# IRQF103C8revA.net
KiCad netlist of a schematic drawn in EAGLE
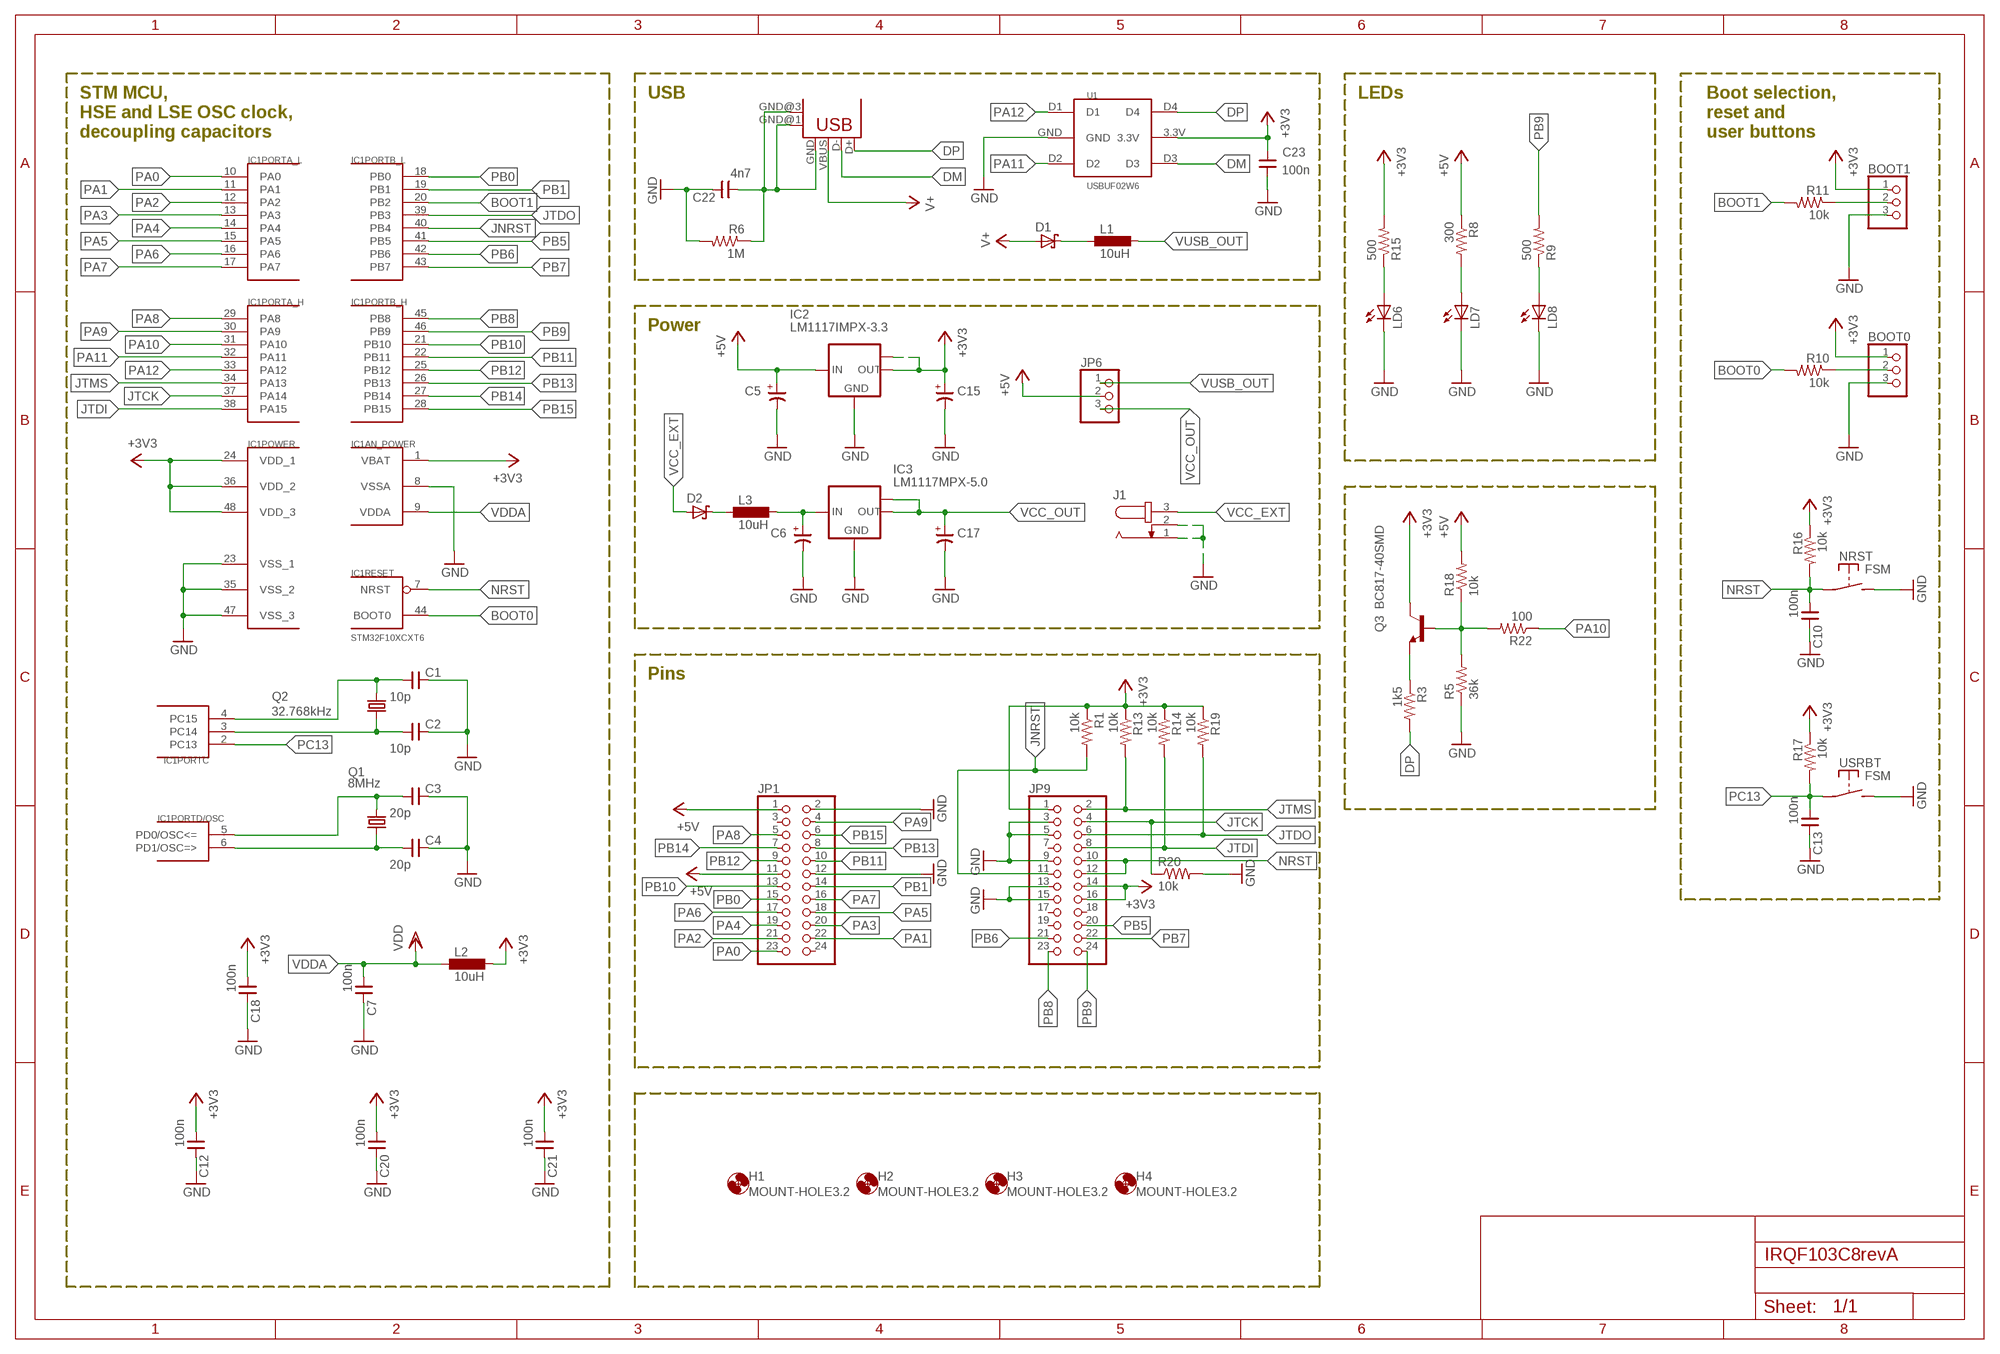
[diagram p0: schematic, sheet 1]

(export (version "E")
  (design (tool "Eeschema 10.0.6"))
  (components
    (comp (ref "BOOT0")
      (value "PINHD-1X3")
      (footprint "eagle-import:1X03")
      (libsource (lib "eagle-import") (part "PINHD-1X3"))
    )
    (comp (ref "BOOT1")
      (value "PINHD-1X3")
      (footprint "eagle-import:1X03")
      (libsource (lib "eagle-import") (part "PINHD-1X3"))
    )
    (comp (ref "C1")
      (value "10p")
      (footprint "eagle-import:0805")
      (libsource (lib "eagle-import") (part "CNP-0805"))
    )
    (comp (ref "C2")
      (value "10p")
      (footprint "eagle-import:0805")
      (libsource (lib "eagle-import") (part "CNP-0805"))
    )
    (comp (ref "C3")
      (value "20p")
      (footprint "eagle-import:0805")
      (libsource (lib "eagle-import") (part "CNP-0805"))
    )
    (comp (ref "C4")
      (value "20p")
      (footprint "eagle-import:0805")
      (libsource (lib "eagle-import") (part "CNP-0805"))
    )
    (comp (ref "C5")
      (value "CP-3258-TE-B")
      (footprint "eagle-import:3528-TE-B")
      (libsource (lib "eagle-import") (part "CP-3258-TE-B"))
    )
    (comp (ref "C6")
      (value "CP-3258-TE-B")
      (footprint "eagle-import:3528-TE-B")
      (libsource (lib "eagle-import") (part "CP-3258-TE-B"))
    )
    (comp (ref "C7")
      (value "100n")
      (footprint "eagle-import:0805")
      (libsource (lib "eagle-import") (part "CNP-0805"))
    )
    (comp (ref "C10")
      (value "100n")
      (footprint "eagle-import:0805")
      (libsource (lib "eagle-import") (part "CNP-0805"))
    )
    (comp (ref "C12")
      (value "100n")
      (footprint "eagle-import:0805")
      (libsource (lib "eagle-import") (part "CNP-0805"))
    )
    (comp (ref "C13")
      (value "100n")
      (footprint "eagle-import:0805")
      (libsource (lib "eagle-import") (part "CNP-0805"))
    )
    (comp (ref "C15")
      (value "CP-3216-TE-A")
      (footprint "eagle-import:3216-TE-A")
      (libsource (lib "eagle-import") (part "CP-3216-TE-A"))
    )
    (comp (ref "C17")
      (value "CP-3216-TE-A")
      (footprint "eagle-import:3216-TE-A")
      (libsource (lib "eagle-import") (part "CP-3216-TE-A"))
    )
    (comp (ref "C18")
      (value "100n")
      (footprint "eagle-import:0805")
      (libsource (lib "eagle-import") (part "CNP-0805"))
    )
    (comp (ref "C20")
      (value "100n")
      (footprint "eagle-import:0805")
      (libsource (lib "eagle-import") (part "CNP-0805"))
    )
    (comp (ref "C21")
      (value "100n")
      (footprint "eagle-import:0805")
      (libsource (lib "eagle-import") (part "CNP-0805"))
    )
    (comp (ref "C22")
      (value "4n7")
      (footprint "eagle-import:0805")
      (libsource (lib "eagle-import") (part "CNP-0805"))
    )
    (comp (ref "C23")
      (value "100n")
      (footprint "eagle-import:0805")
      (libsource (lib "eagle-import") (part "CNP-0805"))
    )
    (comp (ref "D1")
      (value "SCHOTTKY_SMA")
      (footprint "eagle-import:DIOM5326X292N")
      (libsource (lib "eagle-import") (part "SCHOTTKY_SMA"))
    )
    (comp (ref "D2")
      (value "SCHOTTKY_SMA")
      (footprint "eagle-import:DIOM5326X292N")
      (libsource (lib "eagle-import") (part "SCHOTTKY_SMA"))
    )
    (comp (ref "H1")
      (value "MOUNT-HOLE3.2")
      (footprint "eagle-import:3,2")
      (libsource (lib "eagle-import") (part "MOUNT-HOLE3.2"))
    )
    (comp (ref "H2")
      (value "MOUNT-HOLE3.2")
      (footprint "eagle-import:3,2")
      (libsource (lib "eagle-import") (part "MOUNT-HOLE3.2"))
    )
    (comp (ref "H3")
      (value "MOUNT-HOLE3.2")
      (footprint "eagle-import:3,2")
      (libsource (lib "eagle-import") (part "MOUNT-HOLE3.2"))
    )
    (comp (ref "H4")
      (value "MOUNT-HOLE3.2")
      (footprint "eagle-import:3,2")
      (libsource (lib "eagle-import") (part "MOUNT-HOLE3.2"))
    )
    (comp (ref "IC1")
      (value "STM32F10XCXT6")
      (footprint "eagle-import:TQFP48")
      (libsource (lib "eagle-import") (part "STM32F10XCXT6"))
    )
    (comp (ref "IC2")
      (value "LM1117IMPX-3.3")
      (footprint "eagle-import:SOT223")
      (libsource (lib "eagle-import") (part "LM1117IMPX-3.3"))
    )
    (comp (ref "IC3")
      (value "LM1117MPX-5.0")
      (footprint "eagle-import:SOT223")
      (libsource (lib "eagle-import") (part "LM1117MPX-5.0"))
    )
    (comp (ref "J1")
      (value "JACK-PLUG1")
      (footprint "eagle-import:SPC4078")
      (libsource (lib "eagle-import") (part "JACK-PLUG1"))
    )
    (comp (ref "JP1")
      (value "PINHD-2X12")
      (footprint "eagle-import:2X12")
      (libsource (lib "eagle-import") (part "PINHD-2X12"))
    )
    (comp (ref "JP6")
      (value "PINHD-1X3")
      (footprint "eagle-import:1X03")
      (libsource (lib "eagle-import") (part "PINHD-1X3"))
    )
    (comp (ref "JP9")
      (value "PINHD-2X12")
      (footprint "eagle-import:2X12")
      (libsource (lib "eagle-import") (part "PINHD-2X12"))
    )
    (comp (ref "L1")
      (value "10uH")
      (footprint "eagle-import:INDC1608X95N")
      (libsource (lib "eagle-import") (part "INDUCTOR_0603"))
    )
    (comp (ref "L2")
      (value "10uH")
      (footprint "eagle-import:INDC1608X95N")
      (libsource (lib "eagle-import") (part "INDUCTOR_0603"))
    )
    (comp (ref "L3")
      (value "10uH")
      (footprint "eagle-import:INDC1608X95N")
      (libsource (lib "eagle-import") (part "INDUCTOR_0603"))
    )
    (comp (ref "LD6")
      (value "LEDCHIPLED_0805")
      (footprint "eagle-import:CHIPLED_0805")
      (libsource (lib "eagle-import") (part "LEDCHIPLED_0805"))
    )
    (comp (ref "LD7")
      (value "LEDCHIPLED_0805")
      (footprint "eagle-import:CHIPLED_0805")
      (libsource (lib "eagle-import") (part "LEDCHIPLED_0805"))
    )
    (comp (ref "LD8")
      (value "LEDCHIPLED_0805")
      (footprint "eagle-import:CHIPLED_0805")
      (libsource (lib "eagle-import") (part "LEDCHIPLED_0805"))
    )
    (comp (ref "NRST")
      (value "FSM")
      (footprint "eagle-import:FSM")
      (libsource (lib "eagle-import") (part "FSM"))
    )
    (comp (ref "Q1")
      (value "8MHz")
      (footprint "eagle-import:HC49_S")
      (libsource (lib "eagle-import") (part "CRYTALHC49S"))
    )
    (comp (ref "Q2")
      (value "32.768kHz")
      (footprint "eagle-import:TC26H")
      (libsource (lib "eagle-import") (part "CRYTALTC26H"))
    )
    (comp (ref "Q3")
      (value "BC817-40SMD")
      (footprint "eagle-import:SOT23-BEC")
      (libsource (lib "eagle-import") (part "BC817SMD-40"))
    )
    (comp (ref "R1")
      (value "10k")
      (footprint "eagle-import:M0805")
      (libsource (lib "eagle-import") (part "R-US_M0805"))
    )
    (comp (ref "R3")
      (value "1k5")
      (footprint "eagle-import:M0805")
      (libsource (lib "eagle-import") (part "R-US_M0805"))
    )
    (comp (ref "R5")
      (value "36k")
      (footprint "eagle-import:M0805")
      (libsource (lib "eagle-import") (part "R-US_M0805"))
    )
    (comp (ref "R6")
      (value "1M")
      (footprint "eagle-import:M0805")
      (libsource (lib "eagle-import") (part "R-US_M0805"))
    )
    (comp (ref "R8")
      (value "300")
      (footprint "eagle-import:M0805")
      (libsource (lib "eagle-import") (part "R-US_M0805"))
    )
    (comp (ref "R9")
      (value "500")
      (footprint "eagle-import:M0805")
      (libsource (lib "eagle-import") (part "R-US_M0805"))
    )
    (comp (ref "R10")
      (value "10k")
      (footprint "eagle-import:M0805")
      (libsource (lib "eagle-import") (part "R-US_M0805"))
    )
    (comp (ref "R11")
      (value "10k")
      (footprint "eagle-import:M0805")
      (libsource (lib "eagle-import") (part "R-US_M0805"))
    )
    (comp (ref "R13")
      (value "10k")
      (footprint "eagle-import:M0805")
      (libsource (lib "eagle-import") (part "R-US_M0805"))
    )
    (comp (ref "R14")
      (value "10k")
      (footprint "eagle-import:M0805")
      (libsource (lib "eagle-import") (part "R-US_M0805"))
    )
    (comp (ref "R15")
      (value "500")
      (footprint "eagle-import:M0805")
      (libsource (lib "eagle-import") (part "R-US_M0805"))
    )
    (comp (ref "R16")
      (value "10k")
      (footprint "eagle-import:M0805")
      (libsource (lib "eagle-import") (part "R-US_M0805"))
    )
    (comp (ref "R17")
      (value "10k")
      (footprint "eagle-import:M0805")
      (libsource (lib "eagle-import") (part "R-US_M0805"))
    )
    (comp (ref "R18")
      (value "10k")
      (footprint "eagle-import:M0805")
      (libsource (lib "eagle-import") (part "R-US_M0805"))
    )
    (comp (ref "R19")
      (value "10k")
      (footprint "eagle-import:M0805")
      (libsource (lib "eagle-import") (part "R-US_M0805"))
    )
    (comp (ref "R20")
      (value "10k")
      (footprint "eagle-import:M0805")
      (libsource (lib "eagle-import") (part "R-US_M0805"))
    )
    (comp (ref "R22")
      (value "100")
      (footprint "eagle-import:M0805")
      (libsource (lib "eagle-import") (part "R-US_M0805"))
    )
    (comp (ref "U1")
      (value "USBUF02W6")
      (footprint "eagle-import:SOT23-6L")
      (libsource (lib "eagle-import") (part "USBUF02W6"))
    )
    (comp (ref "USB1")
      (value "USB-MB-S")
      (footprint "eagle-import:USB-MB-S")
      (libsource (lib "eagle-import") (part "USB-MB-S"))
    )
    (comp (ref "USRBT")
      (value "FSM")
      (footprint "eagle-import:FSM")
      (libsource (lib "eagle-import") (part "FSM"))
    )
  )
  (nets
    (net (code "1") (name "+3V3") (class "Default")
      (node (ref "BOOT0") (pin "1") (pinfunction "1_1") (pintype "passive"))
      (node (ref "BOOT1") (pin "1") (pinfunction "1_1") (pintype "passive"))
      (node (ref "C12") (pin "1") (pinfunction "1_1") (pintype "passive"))
      (node (ref "C15") (pin "+") (pinfunction "+_+") (pintype "passive"))
      (node (ref "C18") (pin "1") (pinfunction "1_1") (pintype "passive"))
      (node (ref "C20") (pin "1") (pinfunction "1_1") (pintype "passive"))
      (node (ref "C21") (pin "1") (pinfunction "1_1") (pintype "passive"))
      (node (ref "C23") (pin "1") (pinfunction "1_1") (pintype "passive"))
      (node (ref "IC1") (pin "1") (pinfunction "VBAT_1") (pintype "power_in"))
      (node (ref "IC1") (pin "24") (pinfunction "VDD_1_24") (pintype "power_in"))
      (node (ref "IC1") (pin "36") (pinfunction "VDD_2_36") (pintype "power_in"))
      (node (ref "IC1") (pin "48") (pinfunction "VDD_3_48") (pintype "power_in"))
      (node (ref "IC2") (pin "2") (pinfunction "OUT_2") (pintype "passive"))
      (node (ref "IC2") (pin "TAB") (pinfunction "OUT1_TAB") (pintype "passive"))
      (node (ref "JP9") (pin "1") (pinfunction "1_1") (pintype "passive"))
      (node (ref "JP9") (pin "14") (pinfunction "14_14") (pintype "passive"))
      (node (ref "JP9") (pin "16") (pinfunction "16_16") (pintype "passive"))
      (node (ref "L2") (pin "2") (pinfunction "2_2") (pintype "passive"))
      (node (ref "Q3") (pin "C") (pinfunction "C_C") (pintype "passive"))
      (node (ref "R1") (pin "1") (pinfunction "1_1") (pintype "passive"))
      (node (ref "R13") (pin "1") (pinfunction "1_1") (pintype "passive"))
      (node (ref "R14") (pin "1") (pinfunction "1_1") (pintype "passive"))
      (node (ref "R15") (pin "2") (pinfunction "2_2") (pintype "passive"))
      (node (ref "R16") (pin "1") (pinfunction "1_1") (pintype "passive"))
      (node (ref "R17") (pin "1") (pinfunction "1_1") (pintype "passive"))
      (node (ref "R19") (pin "1") (pinfunction "1_1") (pintype "passive"))
      (node (ref "U1") (pin "3.3V") (pinfunction "3.3V_3.3V") (pintype "bidirectional"))
    )
    (net (code "2") (name "+5V") (class "Default")
      (node (ref "C5") (pin "+") (pinfunction "+_+") (pintype "passive"))
      (node (ref "IC2") (pin "3") (pinfunction "IN_3") (pintype "input"))
      (node (ref "JP1") (pin "1") (pinfunction "1_1") (pintype "passive"))
      (node (ref "JP1") (pin "11") (pinfunction "11_11") (pintype "passive"))
      (node (ref "JP6") (pin "2") (pinfunction "2_2") (pintype "passive"))
      (node (ref "R18") (pin "2") (pinfunction "2_2") (pintype "passive"))
      (node (ref "R8") (pin "1") (pinfunction "1_1") (pintype "passive"))
    )
    (net (code "3") (name "BOOT0") (class "Default")
      (node (ref "IC1") (pin "44") (pinfunction "BOOT0_44") (pintype "input"))
      (node (ref "R10") (pin "2") (pinfunction "2_2") (pintype "passive"))
    )
    (net (code "4") (name "BOOT1") (class "Default")
      (node (ref "IC1") (pin "20") (pinfunction "PB2_20") (pintype "bidirectional"))
      (node (ref "R11") (pin "2") (pinfunction "2_2") (pintype "passive"))
    )
    (net (code "5") (name "DM") (class "Default")
      (node (ref "U1") (pin "D3") (pinfunction "D3_D3") (pintype "bidirectional"))
      (node (ref "USB1") (pin "D-") (pinfunction "D-_D-") (pintype "bidirectional"))
    )
    (net (code "6") (name "DP") (class "Default")
      (node (ref "R3") (pin "2") (pinfunction "2_2") (pintype "passive"))
      (node (ref "U1") (pin "D4") (pinfunction "D4_D4") (pintype "bidirectional"))
      (node (ref "USB1") (pin "D+") (pinfunction "D+_D+") (pintype "bidirectional"))
    )
    (net (code "7") (name "GND") (class "Default")
      (node (ref "BOOT0") (pin "3") (pinfunction "3_3") (pintype "passive"))
      (node (ref "BOOT1") (pin "3") (pinfunction "3_3") (pintype "passive"))
      (node (ref "C1") (pin "2") (pinfunction "2_2") (pintype "passive"))
      (node (ref "C10") (pin "2") (pinfunction "2_2") (pintype "passive"))
      (node (ref "C12") (pin "2") (pinfunction "2_2") (pintype "passive"))
      (node (ref "C13") (pin "2") (pinfunction "2_2") (pintype "passive"))
      (node (ref "C15") (pin "-") (pinfunction "-_-") (pintype "passive"))
      (node (ref "C17") (pin "-") (pinfunction "-_-") (pintype "passive"))
      (node (ref "C18") (pin "2") (pinfunction "2_2") (pintype "passive"))
      (node (ref "C2") (pin "2") (pinfunction "2_2") (pintype "passive"))
      (node (ref "C20") (pin "2") (pinfunction "2_2") (pintype "passive"))
      (node (ref "C21") (pin "2") (pinfunction "2_2") (pintype "passive"))
      (node (ref "C22") (pin "2") (pinfunction "2_2") (pintype "passive"))
      (node (ref "C23") (pin "2") (pinfunction "2_2") (pintype "passive"))
      (node (ref "C3") (pin "2") (pinfunction "2_2") (pintype "passive"))
      (node (ref "C4") (pin "2") (pinfunction "2_2") (pintype "passive"))
      (node (ref "C5") (pin "-") (pinfunction "-_-") (pintype "passive"))
      (node (ref "C6") (pin "-") (pinfunction "-_-") (pintype "passive"))
      (node (ref "C7") (pin "2") (pinfunction "2_2") (pintype "passive"))
      (node (ref "IC1") (pin "23") (pinfunction "VSS_1_23") (pintype "power_in"))
      (node (ref "IC1") (pin "35") (pinfunction "VSS_2_35") (pintype "power_in"))
      (node (ref "IC1") (pin "47") (pinfunction "VSS_3_47") (pintype "power_in"))
      (node (ref "IC1") (pin "8") (pinfunction "VSSA_8") (pintype "power_in"))
      (node (ref "IC2") (pin "1") (pinfunction "GND_1") (pintype "input"))
      (node (ref "IC3") (pin "1") (pinfunction "GND_1") (pintype "input"))
      (node (ref "J1") (pin "1") (pinfunction "1_1") (pintype "passive"))
      (node (ref "J1") (pin "2") (pinfunction "2_2") (pintype "passive"))
      (node (ref "JP1") (pin "12") (pinfunction "12_12") (pintype "passive"))
      (node (ref "JP1") (pin "2") (pinfunction "2_2") (pintype "passive"))
      (node (ref "JP9") (pin "13") (pinfunction "13_13") (pintype "passive"))
      (node (ref "JP9") (pin "15") (pinfunction "15_15") (pintype "passive"))
      (node (ref "JP9") (pin "3") (pinfunction "3_3") (pintype "passive"))
      (node (ref "JP9") (pin "5") (pinfunction "5_5") (pintype "passive"))
      (node (ref "JP9") (pin "9") (pinfunction "9_9") (pintype "passive"))
      (node (ref "LD6") (pin "C") (pinfunction "C_C") (pintype "passive"))
      (node (ref "LD7") (pin "C") (pinfunction "C_C") (pintype "passive"))
      (node (ref "LD8") (pin "C") (pinfunction "C_C") (pintype "passive"))
      (node (ref "NRST") (pin "P$2") (pinfunction "S_P$2") (pintype "passive"))
      (node (ref "R20") (pin "2") (pinfunction "2_2") (pintype "passive"))
      (node (ref "R5") (pin "1") (pinfunction "1_1") (pintype "passive"))
      (node (ref "R6") (pin "2") (pinfunction "2_2") (pintype "passive"))
      (node (ref "U1") (pin "GND") (pinfunction "GND_GND") (pintype "bidirectional"))
      (node (ref "USRBT") (pin "P$2") (pinfunction "S_P$2") (pintype "passive"))
    )
    (net (code "8") (name "JNRST") (class "Default")
      (node (ref "IC1") (pin "40") (pinfunction "PB4_40") (pintype "bidirectional"))
      (node (ref "JP9") (pin "11") (pinfunction "11_11") (pintype "passive"))
      (node (ref "R1") (pin "2") (pinfunction "2_2") (pintype "passive"))
    )
    (net (code "9") (name "JTCK") (class "Default")
      (node (ref "IC1") (pin "37") (pinfunction "PA14_37") (pintype "bidirectional"))
      (node (ref "JP9") (pin "4") (pinfunction "4_4") (pintype "passive"))
      (node (ref "R20") (pin "1") (pinfunction "1_1") (pintype "passive"))
    )
    (net (code "10") (name "JTDI") (class "Default")
      (node (ref "IC1") (pin "38") (pinfunction "PA15_38") (pintype "bidirectional"))
      (node (ref "JP9") (pin "8") (pinfunction "8_8") (pintype "passive"))
      (node (ref "R14") (pin "2") (pinfunction "2_2") (pintype "passive"))
    )
    (net (code "11") (name "JTDO") (class "Default")
      (node (ref "IC1") (pin "39") (pinfunction "PB3_39") (pintype "bidirectional"))
      (node (ref "JP9") (pin "6") (pinfunction "6_6") (pintype "passive"))
      (node (ref "R19") (pin "2") (pinfunction "2_2") (pintype "passive"))
    )
    (net (code "12") (name "JTMS") (class "Default")
      (node (ref "IC1") (pin "34") (pinfunction "PA13_34") (pintype "bidirectional"))
      (node (ref "JP9") (pin "2") (pinfunction "2_2") (pintype "passive"))
      (node (ref "R13") (pin "2") (pinfunction "2_2") (pintype "passive"))
    )
    (net (code "13") (name "NRST") (class "Default")
      (node (ref "C10") (pin "1") (pinfunction "1_1") (pintype "passive"))
      (node (ref "IC1") (pin "7") (pinfunction "NRST_7") (pintype "input"))
      (node (ref "JP9") (pin "10") (pinfunction "10_10") (pintype "passive"))
      (node (ref "JP9") (pin "12") (pinfunction "12_12") (pintype "passive"))
      (node (ref "NRST") (pin "P$1") (pinfunction "P_P$1") (pintype "passive"))
      (node (ref "R16") (pin "2") (pinfunction "2_2") (pintype "passive"))
    )
    (net (code "14") (name "Net-(BOOT0-Pad2)") (class "Default")
      (node (ref "BOOT0") (pin "2") (pinfunction "2_2") (pintype "passive"))
      (node (ref "R10") (pin "1") (pinfunction "1_1") (pintype "passive"))
    )
    (net (code "15") (name "Net-(BOOT1-Pad2)") (class "Default")
      (node (ref "BOOT1") (pin "2") (pinfunction "2_2") (pintype "passive"))
      (node (ref "R11") (pin "1") (pinfunction "1_1") (pintype "passive"))
    )
    (net (code "16") (name "Net-(C22-Pad1)") (class "Default")
      (node (ref "C22") (pin "1") (pinfunction "1_1") (pintype "passive"))
      (node (ref "R6") (pin "1") (pinfunction "1_1") (pintype "passive"))
      (node (ref "USB1") (pin "GND") (pinfunction "GND_GND") (pintype "bidirectional"))
      (node (ref "USB1") (pin "GND@1") (pinfunction "GND_GND@1") (pintype "bidirectional"))
      (node (ref "USB1") (pin "GND@3") (pinfunction "GND_GND@3") (pintype "bidirectional"))
    )
    (net (code "17") (name "Net-(D1-PadK)") (class "Default")
      (node (ref "D1") (pin "K") (pinfunction "K_K") (pintype "passive"))
      (node (ref "L1") (pin "1") (pinfunction "1_1") (pintype "passive"))
    )
    (net (code "18") (name "Net-(D2-PadK)") (class "Default")
      (node (ref "D2") (pin "K") (pinfunction "K_K") (pintype "passive"))
      (node (ref "L3") (pin "1") (pinfunction "1_1") (pintype "passive"))
    )
    (net (code "19") (name "Net-(IC1F-PC14)") (class "Default")
      (node (ref "C2") (pin "1") (pinfunction "1_1") (pintype "passive"))
      (node (ref "IC1") (pin "3") (pinfunction "PC14_3") (pintype "bidirectional"))
      (node (ref "Q2") (pin "1") (pinfunction "1_1") (pintype "passive"))
    )
    (net (code "20") (name "Net-(IC1F-PC15)") (class "Default")
      (node (ref "C1") (pin "1") (pinfunction "1_1") (pintype "passive"))
      (node (ref "IC1") (pin "4") (pinfunction "PC15_4") (pintype "bidirectional"))
      (node (ref "Q2") (pin "2") (pinfunction "2_2") (pintype "passive"))
    )
    (net (code "21") (name "Net-(IC1G-PD0{slash}OSC<=)") (class "Default")
      (node (ref "C3") (pin "1") (pinfunction "1_1") (pintype "passive"))
      (node (ref "IC1") (pin "5") (pinfunction "PD0/OSC<=_5") (pintype "bidirectional"))
      (node (ref "Q1") (pin "2") (pinfunction "2_2") (pintype "passive"))
    )
    (net (code "22") (name "Net-(IC1G-PD1{slash}OSC=>)") (class "Default")
      (node (ref "C4") (pin "1") (pinfunction "1_1") (pintype "passive"))
      (node (ref "IC1") (pin "6") (pinfunction "PD1/OSC=>_6") (pintype "bidirectional"))
      (node (ref "Q1") (pin "1") (pinfunction "1_1") (pintype "passive"))
    )
    (net (code "23") (name "Net-(IC3-IN)") (class "Default")
      (node (ref "C6") (pin "+") (pinfunction "+_+") (pintype "passive"))
      (node (ref "IC3") (pin "3") (pinfunction "IN_3") (pintype "input"))
      (node (ref "L3") (pin "2") (pinfunction "2_2") (pintype "passive"))
    )
    (net (code "24") (name "Net-(LD6-PadA)") (class "Default")
      (node (ref "LD6") (pin "A") (pinfunction "A_A") (pintype "passive"))
      (node (ref "R15") (pin "1") (pinfunction "1_1") (pintype "passive"))
    )
    (net (code "25") (name "Net-(LD7-PadA)") (class "Default")
      (node (ref "LD7") (pin "A") (pinfunction "A_A") (pintype "passive"))
      (node (ref "R8") (pin "2") (pinfunction "2_2") (pintype "passive"))
    )
    (net (code "26") (name "Net-(LD8-PadA)") (class "Default")
      (node (ref "LD8") (pin "A") (pinfunction "A_A") (pintype "passive"))
      (node (ref "R9") (pin "1") (pinfunction "1_1") (pintype "passive"))
    )
    (net (code "27") (name "Net-(Q3-PadB)") (class "Default")
      (node (ref "Q3") (pin "B") (pinfunction "B_B") (pintype "passive"))
      (node (ref "R18") (pin "1") (pinfunction "1_1") (pintype "passive"))
      (node (ref "R22") (pin "2") (pinfunction "2_2") (pintype "passive"))
      (node (ref "R5") (pin "2") (pinfunction "2_2") (pintype "passive"))
    )
    (net (code "28") (name "Net-(Q3-PadE)") (class "Default")
      (node (ref "Q3") (pin "E") (pinfunction "E_E") (pintype "passive"))
      (node (ref "R3") (pin "1") (pinfunction "1_1") (pintype "passive"))
    )
    (net (code "29") (name "PA0") (class "Default")
      (node (ref "IC1") (pin "10") (pinfunction "PA0_10") (pintype "bidirectional"))
      (node (ref "JP1") (pin "23") (pinfunction "23_23") (pintype "passive"))
    )
    (net (code "30") (name "PA1") (class "Default")
      (node (ref "IC1") (pin "11") (pinfunction "PA1_11") (pintype "bidirectional"))
      (node (ref "JP1") (pin "22") (pinfunction "22_22") (pintype "passive"))
    )
    (net (code "31") (name "PA2") (class "Default")
      (node (ref "IC1") (pin "12") (pinfunction "PA2_12") (pintype "bidirectional"))
      (node (ref "JP1") (pin "21") (pinfunction "21_21") (pintype "passive"))
    )
    (net (code "32") (name "PA3") (class "Default")
      (node (ref "IC1") (pin "13") (pinfunction "PA3_13") (pintype "bidirectional"))
      (node (ref "JP1") (pin "20") (pinfunction "20_20") (pintype "passive"))
    )
    (net (code "33") (name "PA4") (class "Default")
      (node (ref "IC1") (pin "14") (pinfunction "PA4_14") (pintype "bidirectional"))
      (node (ref "JP1") (pin "19") (pinfunction "19_19") (pintype "passive"))
    )
    (net (code "34") (name "PA5") (class "Default")
      (node (ref "IC1") (pin "15") (pinfunction "PA5_15") (pintype "bidirectional"))
      (node (ref "JP1") (pin "18") (pinfunction "18_18") (pintype "passive"))
    )
    (net (code "35") (name "PA6") (class "Default")
      (node (ref "IC1") (pin "16") (pinfunction "PA6_16") (pintype "bidirectional"))
      (node (ref "JP1") (pin "17") (pinfunction "17_17") (pintype "passive"))
    )
    (net (code "36") (name "PA7") (class "Default")
      (node (ref "IC1") (pin "17") (pinfunction "PA7_17") (pintype "bidirectional"))
      (node (ref "JP1") (pin "16") (pinfunction "16_16") (pintype "passive"))
    )
    (net (code "37") (name "PA8") (class "Default")
      (node (ref "IC1") (pin "29") (pinfunction "PA8_29") (pintype "bidirectional"))
      (node (ref "JP1") (pin "5") (pinfunction "5_5") (pintype "passive"))
    )
    (net (code "38") (name "PA9") (class "Default")
      (node (ref "IC1") (pin "30") (pinfunction "PA9_30") (pintype "bidirectional"))
      (node (ref "JP1") (pin "4") (pinfunction "4_4") (pintype "passive"))
    )
    (net (code "39") (name "PA10") (class "Default")
      (node (ref "IC1") (pin "31") (pinfunction "PA10_31") (pintype "bidirectional"))
      (node (ref "R22") (pin "1") (pinfunction "1_1") (pintype "passive"))
    )
    (net (code "40") (name "PA11") (class "Default")
      (node (ref "IC1") (pin "32") (pinfunction "PA11_32") (pintype "bidirectional"))
      (node (ref "U1") (pin "D2") (pinfunction "D2_D2") (pintype "bidirectional"))
    )
    (net (code "41") (name "PA12") (class "Default")
      (node (ref "IC1") (pin "33") (pinfunction "PA12_33") (pintype "bidirectional"))
      (node (ref "U1") (pin "D1") (pinfunction "D1_D1") (pintype "bidirectional"))
    )
    (net (code "42") (name "PB0") (class "Default")
      (node (ref "IC1") (pin "18") (pinfunction "PB0_18") (pintype "bidirectional"))
      (node (ref "JP1") (pin "15") (pinfunction "15_15") (pintype "passive"))
    )
    (net (code "43") (name "PB1") (class "Default")
      (node (ref "IC1") (pin "19") (pinfunction "PB1_19") (pintype "bidirectional"))
      (node (ref "JP1") (pin "14") (pinfunction "14_14") (pintype "passive"))
    )
    (net (code "44") (name "PB5") (class "Default")
      (node (ref "IC1") (pin "41") (pinfunction "PB5_41") (pintype "bidirectional"))
      (node (ref "JP9") (pin "20") (pinfunction "20_20") (pintype "passive"))
    )
    (net (code "45") (name "PB6") (class "Default")
      (node (ref "IC1") (pin "42") (pinfunction "PB6_42") (pintype "bidirectional"))
      (node (ref "JP9") (pin "21") (pinfunction "21_21") (pintype "passive"))
    )
    (net (code "46") (name "PB7") (class "Default")
      (node (ref "IC1") (pin "43") (pinfunction "PB7_43") (pintype "bidirectional"))
      (node (ref "JP9") (pin "22") (pinfunction "22_22") (pintype "passive"))
    )
    (net (code "47") (name "PB8") (class "Default")
      (node (ref "IC1") (pin "45") (pinfunction "PB8_45") (pintype "bidirectional"))
      (node (ref "JP9") (pin "23") (pinfunction "23_23") (pintype "passive"))
    )
    (net (code "48") (name "PB9") (class "Default")
      (node (ref "IC1") (pin "46") (pinfunction "PB9_46") (pintype "bidirectional"))
      (node (ref "JP9") (pin "24") (pinfunction "24_24") (pintype "passive"))
      (node (ref "R9") (pin "2") (pinfunction "2_2") (pintype "passive"))
    )
    (net (code "49") (name "PB10") (class "Default")
      (node (ref "IC1") (pin "21") (pinfunction "PB10_21") (pintype "bidirectional"))
      (node (ref "JP1") (pin "13") (pinfunction "13_13") (pintype "passive"))
    )
    (net (code "50") (name "PB11") (class "Default")
      (node (ref "IC1") (pin "22") (pinfunction "PB11_22") (pintype "bidirectional"))
      (node (ref "JP1") (pin "10") (pinfunction "10_10") (pintype "passive"))
    )
    (net (code "51") (name "PB12") (class "Default")
      (node (ref "IC1") (pin "25") (pinfunction "PB12_25") (pintype "bidirectional"))
      (node (ref "JP1") (pin "9") (pinfunction "9_9") (pintype "passive"))
    )
    (net (code "52") (name "PB13") (class "Default")
      (node (ref "IC1") (pin "26") (pinfunction "PB13_26") (pintype "bidirectional"))
      (node (ref "JP1") (pin "8") (pinfunction "8_8") (pintype "passive"))
    )
    (net (code "53") (name "PB14") (class "Default")
      (node (ref "IC1") (pin "27") (pinfunction "PB14_27") (pintype "bidirectional"))
      (node (ref "JP1") (pin "7") (pinfunction "7_7") (pintype "passive"))
    )
    (net (code "54") (name "PB15") (class "Default")
      (node (ref "IC1") (pin "28") (pinfunction "PB15_28") (pintype "bidirectional"))
      (node (ref "JP1") (pin "6") (pinfunction "6_6") (pintype "passive"))
    )
    (net (code "55") (name "PC13") (class "Default")
      (node (ref "C13") (pin "1") (pinfunction "1_1") (pintype "passive"))
      (node (ref "IC1") (pin "2") (pinfunction "PC13_2") (pintype "bidirectional"))
      (node (ref "R17") (pin "2") (pinfunction "2_2") (pintype "passive"))
      (node (ref "USRBT") (pin "P$1") (pinfunction "P_P$1") (pintype "passive"))
    )
    (net (code "56") (name "V+") (class "Default")
      (node (ref "D1") (pin "A") (pinfunction "A_A") (pintype "passive"))
      (node (ref "USB1") (pin "VBUS") (pinfunction "VBUS_VBUS") (pintype "bidirectional"))
    )
    (net (code "57") (name "VCC_EXT") (class "Default")
      (node (ref "D2") (pin "A") (pinfunction "A_A") (pintype "passive"))
      (node (ref "J1") (pin "3") (pinfunction "3_3") (pintype "passive"))
    )
    (net (code "58") (name "VCC_OUT") (class "Default")
      (node (ref "C17") (pin "+") (pinfunction "+_+") (pintype "passive"))
      (node (ref "IC3") (pin "2") (pinfunction "OUT_2") (pintype "passive"))
      (node (ref "IC3") (pin "TAB") (pinfunction "OUT1_TAB") (pintype "passive"))
      (node (ref "JP6") (pin "3") (pinfunction "3_3") (pintype "passive"))
    )
    (net (code "59") (name "VDDA") (class "Default")
      (node (ref "C7") (pin "1") (pinfunction "1_1") (pintype "passive"))
      (node (ref "IC1") (pin "9") (pinfunction "VDDA_9") (pintype "power_in"))
      (node (ref "L2") (pin "1") (pinfunction "1_1") (pintype "passive"))
    )
    (net (code "60") (name "VUSB_OUT") (class "Default")
      (node (ref "JP6") (pin "1") (pinfunction "1_1") (pintype "passive"))
      (node (ref "L1") (pin "2") (pinfunction "2_2") (pintype "passive"))
    )
    (net (code "61") (name "unconnected-(JP1-Pad3)") (class "Default")
      (node (ref "JP1") (pin "3") (pinfunction "3_3") (pintype "passive"))
    )
    (net (code "62") (name "unconnected-(JP1-Pad24)") (class "Default")
      (node (ref "JP1") (pin "24") (pinfunction "24_24") (pintype "passive"))
    )
    (net (code "63") (name "unconnected-(JP9-Pad7)") (class "Default")
      (node (ref "JP9") (pin "7") (pinfunction "7_7") (pintype "passive"))
    )
    (net (code "64") (name "unconnected-(JP9-Pad17)") (class "Default")
      (node (ref "JP9") (pin "17") (pinfunction "17_17") (pintype "passive"))
    )
    (net (code "65") (name "unconnected-(JP9-Pad18)") (class "Default")
      (node (ref "JP9") (pin "18") (pinfunction "18_18") (pintype "passive"))
    )
    (net (code "66") (name "unconnected-(JP9-Pad19)") (class "Default")
      (node (ref "JP9") (pin "19") (pinfunction "19_19") (pintype "passive"))
    )
  )
)
